# mainboard.net
KiCad netlist of a schematic drawn in EAGLE
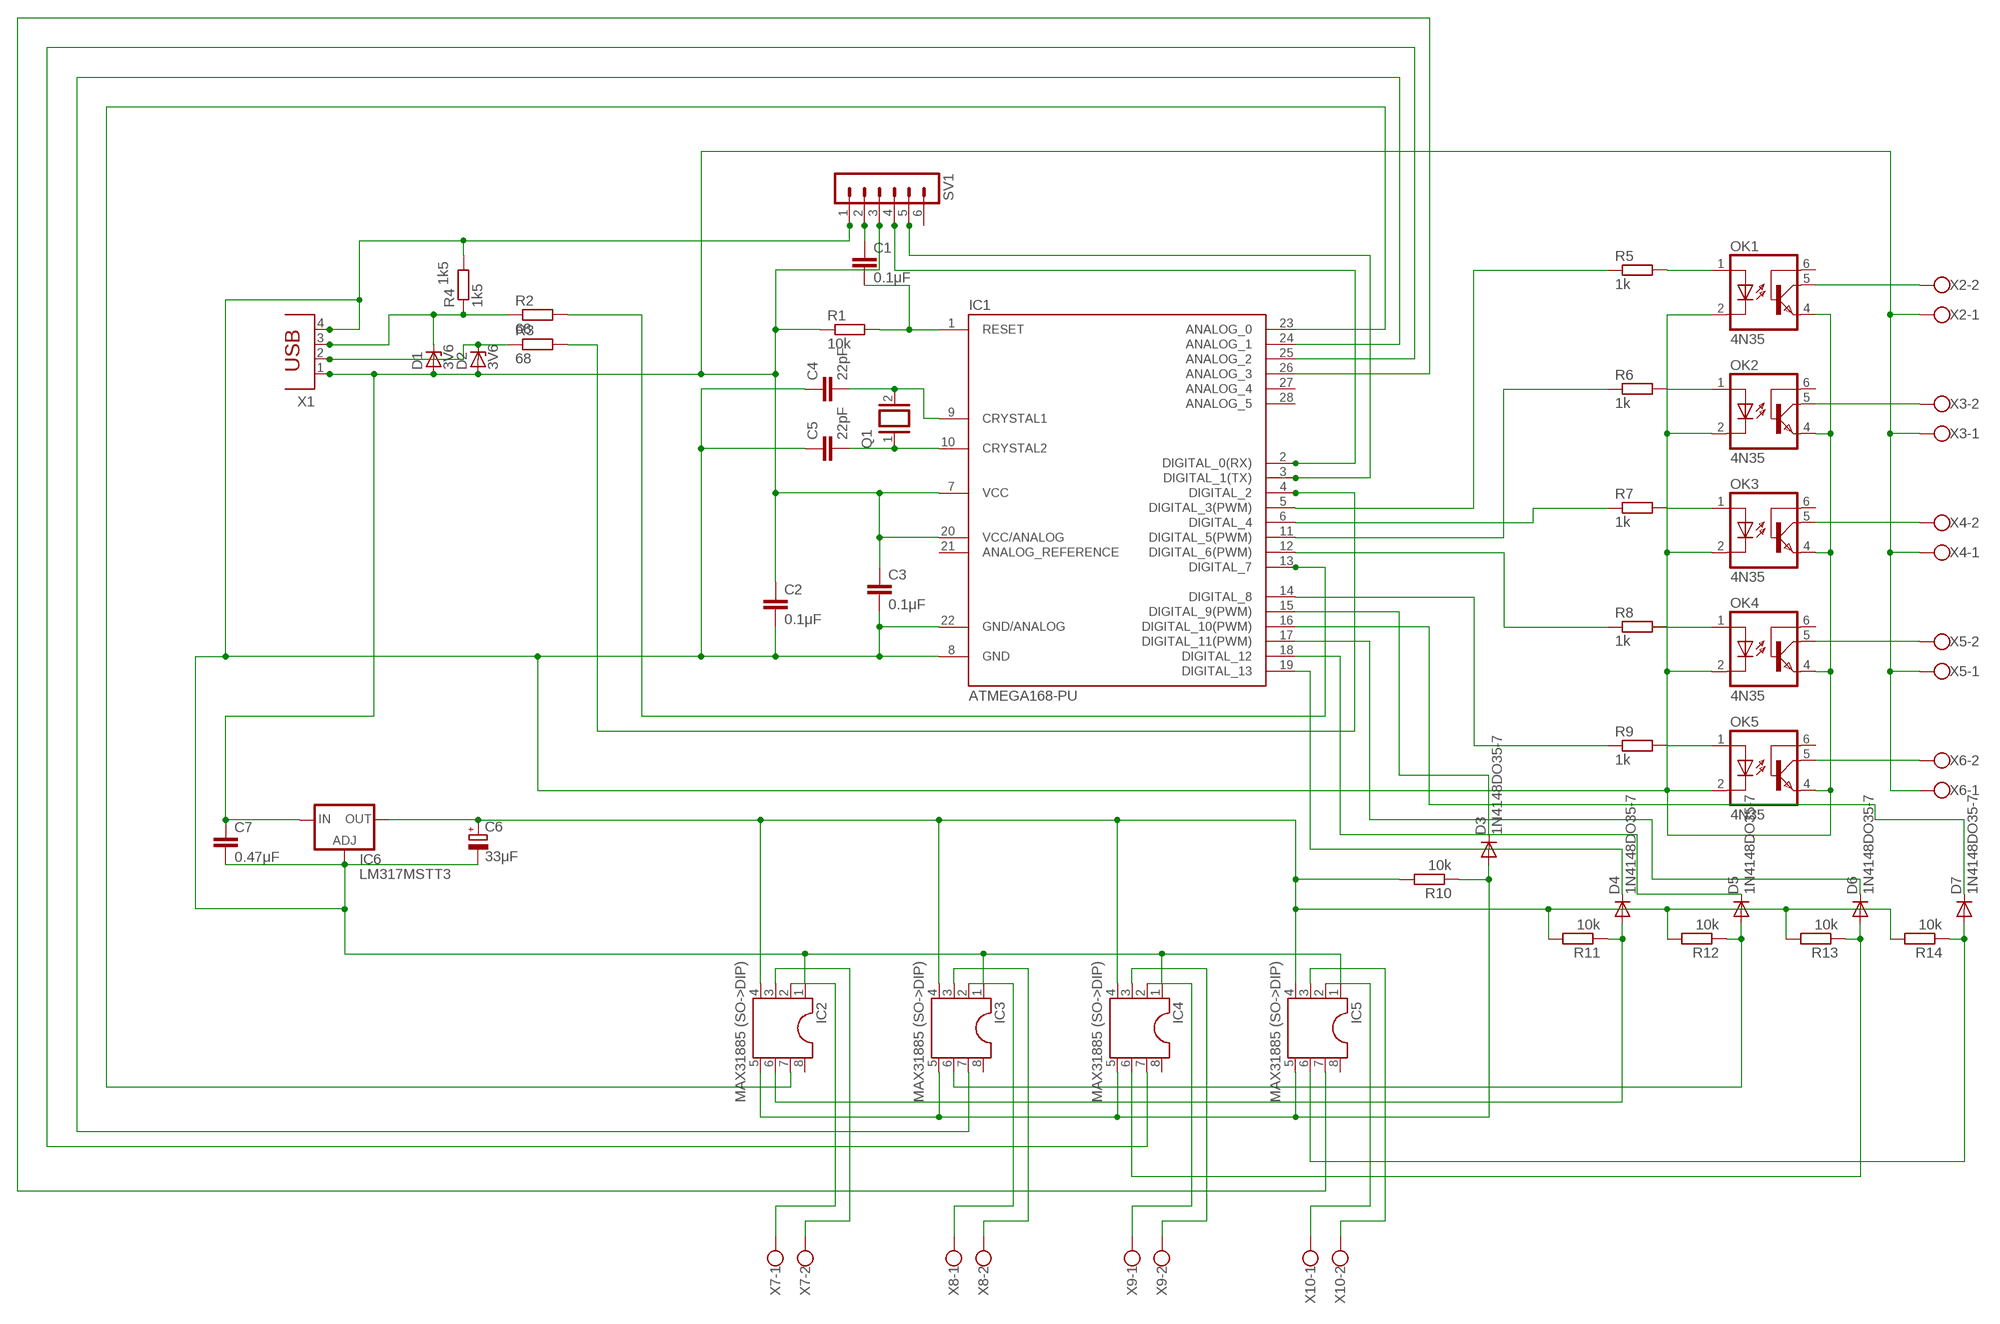
[diagram p0: schematic, sheet 1]

(export (version "E")
  (design (tool "Eeschema 10.0.6"))
  (components
    (comp (ref "C1")
      (value "0.1μF")
      (footprint "eagle-import:C2.5-3")
      (libsource (lib "eagle-import") (part "C2,5-3"))
    )
    (comp (ref "C2")
      (value "0.1μF")
      (footprint "eagle-import:C2.5-3")
      (libsource (lib "eagle-import") (part "C2,5-3"))
    )
    (comp (ref "C3")
      (value "0.1μF")
      (footprint "eagle-import:C2.5-3")
      (libsource (lib "eagle-import") (part "C2,5-3"))
    )
    (comp (ref "C4")
      (value "22pF")
      (footprint "eagle-import:C2.5-3")
      (libsource (lib "eagle-import") (part "C2,5-3"))
    )
    (comp (ref "C5")
      (value "22pF")
      (footprint "eagle-import:C2.5-3")
      (libsource (lib "eagle-import") (part "C2,5-3"))
    )
    (comp (ref "C6")
      (value "33μF")
      (footprint "eagle-import:153CLV-0605")
      (libsource (lib "eagle-import") (part "CPOL-EU153CLV-0605"))
    )
    (comp (ref "C7")
      (value "0.47μF")
      (footprint "eagle-import:C2.5-3")
      (libsource (lib "eagle-import") (part "C2,5-3"))
    )
    (comp (ref "D1")
      (value "3V6")
      (footprint "eagle-import:ZDIO-5")
      (libsource (lib "eagle-import") (part "ZENER-DIODEZD-5"))
    )
    (comp (ref "D2")
      (value "3V6")
      (footprint "eagle-import:ZDIO-5")
      (libsource (lib "eagle-import") (part "ZENER-DIODEZD-5"))
    )
    (comp (ref "D3")
      (value "1N4148DO35-7")
      (footprint "eagle-import:DO35-7")
      (libsource (lib "eagle-import") (part "1N4148DO35-7"))
    )
    (comp (ref "D4")
      (value "1N4148DO35-7")
      (footprint "eagle-import:DO35-7")
      (libsource (lib "eagle-import") (part "1N4148DO35-7"))
    )
    (comp (ref "D5")
      (value "1N4148DO35-7")
      (footprint "eagle-import:DO35-7")
      (libsource (lib "eagle-import") (part "1N4148DO35-7"))
    )
    (comp (ref "D6")
      (value "1N4148DO35-7")
      (footprint "eagle-import:DO35-7")
      (libsource (lib "eagle-import") (part "1N4148DO35-7"))
    )
    (comp (ref "D7")
      (value "1N4148DO35-7")
      (footprint "eagle-import:DO35-7")
      (libsource (lib "eagle-import") (part "1N4148DO35-7"))
    )
    (comp (ref "IC1")
      (value "ATMEGA168-PU")
      (footprint "eagle-import:DIL28-3")
      (libsource (lib "eagle-import") (part "ATMEGA168-PU"))
    )
    (comp (ref "IC2")
      (value "DIL8S")
      (footprint "eagle-import:SOCKET-08")
      (libsource (lib "eagle-import") (part "DIL8S"))
    )
    (comp (ref "IC3")
      (value "DIL8S")
      (footprint "eagle-import:SOCKET-08")
      (libsource (lib "eagle-import") (part "DIL8S"))
    )
    (comp (ref "IC4")
      (value "DIL8S")
      (footprint "eagle-import:SOCKET-08")
      (libsource (lib "eagle-import") (part "DIL8S"))
    )
    (comp (ref "IC5")
      (value "DIL8S")
      (footprint "eagle-import:SOCKET-08")
      (libsource (lib "eagle-import") (part "DIL8S"))
    )
    (comp (ref "IC6")
      (value "LM317MSTT3")
      (footprint "eagle-import:SOT223")
      (libsource (lib "eagle-import") (part "LM317?MSTT3"))
    )
    (comp (ref "OK1")
      (value "4N35")
      (footprint "eagle-import:DIL06")
      (fields (field (name "MF") "FAIRCHILD SEMICONDUCTOR"))
      (libsource (lib "eagle-import") (part "4N35"))
    )
    (comp (ref "OK2")
      (value "4N35")
      (footprint "eagle-import:DIL06")
      (fields (field (name "MF") "FAIRCHILD SEMICONDUCTOR"))
      (libsource (lib "eagle-import") (part "4N35"))
    )
    (comp (ref "OK3")
      (value "4N35")
      (footprint "eagle-import:DIL06")
      (fields (field (name "MF") "FAIRCHILD SEMICONDUCTOR"))
      (libsource (lib "eagle-import") (part "4N35"))
    )
    (comp (ref "OK4")
      (value "4N35")
      (footprint "eagle-import:DIL06")
      (fields (field (name "MF") "FAIRCHILD SEMICONDUCTOR"))
      (libsource (lib "eagle-import") (part "4N35"))
    )
    (comp (ref "OK5")
      (value "4N35")
      (footprint "eagle-import:DIL06")
      (fields (field (name "MF") "FAIRCHILD SEMICONDUCTOR"))
      (libsource (lib "eagle-import") (part "4N35"))
    )
    (comp (ref "Q1")
      (value "XTAL/S")
      (footprint "eagle-import:QS")
      (libsource (lib "eagle-import") (part "XTAL/S"))
    )
    (comp (ref "R1")
      (value "10k")
      (footprint "eagle-import:0204_7")
      (libsource (lib "eagle-import") (part "R-EU_0204/7"))
    )
    (comp (ref "R2")
      (value "68")
      (footprint "eagle-import:0204_7")
      (libsource (lib "eagle-import") (part "R-EU_0204/7"))
    )
    (comp (ref "R3")
      (value "68")
      (footprint "eagle-import:0204_7")
      (libsource (lib "eagle-import") (part "R-EU_0204/7"))
    )
    (comp (ref "R4")
      (value "1k5")
      (footprint "eagle-import:0204_7")
      (libsource (lib "eagle-import") (part "R-EU_0204/7"))
    )
    (comp (ref "R5")
      (value "1k")
      (footprint "eagle-import:0204_7")
      (libsource (lib "eagle-import") (part "R-EU_0204/7"))
    )
    (comp (ref "R6")
      (value "1k")
      (footprint "eagle-import:0204_7")
      (libsource (lib "eagle-import") (part "R-EU_0204/7"))
    )
    (comp (ref "R7")
      (value "1k")
      (footprint "eagle-import:0204_7")
      (libsource (lib "eagle-import") (part "R-EU_0204/7"))
    )
    (comp (ref "R8")
      (value "1k")
      (footprint "eagle-import:0204_7")
      (libsource (lib "eagle-import") (part "R-EU_0204/7"))
    )
    (comp (ref "R9")
      (value "1k")
      (footprint "eagle-import:0204_7")
      (libsource (lib "eagle-import") (part "R-EU_0204/7"))
    )
    (comp (ref "R10")
      (value "10k")
      (footprint "eagle-import:0204_7")
      (libsource (lib "eagle-import") (part "R-EU_0204/7"))
    )
    (comp (ref "R11")
      (value "10k")
      (footprint "eagle-import:0204_7")
      (libsource (lib "eagle-import") (part "R-EU_0204/7"))
    )
    (comp (ref "R12")
      (value "10k")
      (footprint "eagle-import:0204_7")
      (libsource (lib "eagle-import") (part "R-EU_0204/7"))
    )
    (comp (ref "R13")
      (value "10k")
      (footprint "eagle-import:0204_7")
      (libsource (lib "eagle-import") (part "R-EU_0204/7"))
    )
    (comp (ref "R14")
      (value "10k")
      (footprint "eagle-import:0204_7")
      (libsource (lib "eagle-import") (part "R-EU_0204/7"))
    )
    (comp (ref "SV1")
      (value "MA06-1")
      (footprint "eagle-import:MA06-1")
      (libsource (lib "eagle-import") (part "MA06-1"))
    )
    (comp (ref "X1")
      (value "PN61729")
      (footprint "eagle-import:PN61729")
      (libsource (lib "eagle-import") (part "PN61729"))
    )
    (comp (ref "X2")
      (value "W237-102")
      (footprint "eagle-import:W237-102")
      (fields (field (name "MPN") "237-102"))
      (libsource (lib "eagle-import") (part "W237-102"))
    )
    (comp (ref "X3")
      (value "W237-102")
      (footprint "eagle-import:W237-102")
      (fields (field (name "MPN") "237-102"))
      (libsource (lib "eagle-import") (part "W237-102"))
    )
    (comp (ref "X4")
      (value "W237-102")
      (footprint "eagle-import:W237-102")
      (fields (field (name "MPN") "237-102"))
      (libsource (lib "eagle-import") (part "W237-102"))
    )
    (comp (ref "X5")
      (value "W237-102")
      (footprint "eagle-import:W237-102")
      (fields (field (name "MPN") "237-102"))
      (libsource (lib "eagle-import") (part "W237-102"))
    )
    (comp (ref "X6")
      (value "W237-102")
      (footprint "eagle-import:W237-102")
      (fields (field (name "MPN") "237-102"))
      (libsource (lib "eagle-import") (part "W237-102"))
    )
    (comp (ref "X7")
      (value "W237-102")
      (footprint "eagle-import:W237-102")
      (fields (field (name "MPN") "237-102"))
      (libsource (lib "eagle-import") (part "W237-102"))
    )
    (comp (ref "X8")
      (value "W237-102")
      (footprint "eagle-import:W237-102")
      (fields (field (name "MPN") "237-102"))
      (libsource (lib "eagle-import") (part "W237-102"))
    )
    (comp (ref "X9")
      (value "W237-102")
      (footprint "eagle-import:W237-102")
      (fields (field (name "MPN") "237-102"))
      (libsource (lib "eagle-import") (part "W237-102"))
    )
    (comp (ref "X10")
      (value "W237-102")
      (footprint "eagle-import:W237-102")
      (fields (field (name "MPN") "237-102"))
      (libsource (lib "eagle-import") (part "W237-102"))
    )
  )
  (nets
    (net (code "1") (name "Net-(C1-Pad1)") (class "Default")
      (node (ref "C1") (pin "1") (pinfunction "1_1") (pintype "passive"))
      (node (ref "SV1") (pin "2") (pinfunction "2_2") (pintype "passive"))
    )
    (net (code "2") (name "Net-(D1-PadC)") (class "Default")
      (node (ref "D1") (pin "C") (pinfunction "C_C") (pintype "passive"))
      (node (ref "R2") (pin "1") (pinfunction "1_1") (pintype "passive"))
      (node (ref "R4") (pin "1") (pinfunction "1_1") (pintype "passive"))
      (node (ref "X1") (pin "3") (pinfunction "3_3") (pintype "passive"))
    )
    (net (code "3") (name "Net-(D2-PadC)") (class "Default")
      (node (ref "D2") (pin "C") (pinfunction "C_C") (pintype "passive"))
      (node (ref "R3") (pin "1") (pinfunction "1_1") (pintype "passive"))
      (node (ref "X1") (pin "2") (pinfunction "2_2") (pintype "passive"))
    )
    (net (code "4") (name "Net-(D3-PadA)") (class "Default")
      (node (ref "D3") (pin "A") (pinfunction "A_A") (pintype "passive"))
      (node (ref "IC2") (pin "5") (pinfunction "5_5") (pintype "passive"))
      (node (ref "IC3") (pin "5") (pinfunction "5_5") (pintype "passive"))
      (node (ref "IC4") (pin "5") (pinfunction "5_5") (pintype "passive"))
      (node (ref "IC5") (pin "5") (pinfunction "5_5") (pintype "passive"))
      (node (ref "R10") (pin "1") (pinfunction "1_1") (pintype "passive"))
    )
    (net (code "5") (name "Net-(D4-PadA)") (class "Default")
      (node (ref "D4") (pin "A") (pinfunction "A_A") (pintype "passive"))
      (node (ref "IC2") (pin "6") (pinfunction "6_6") (pintype "passive"))
      (node (ref "R11") (pin "1") (pinfunction "1_1") (pintype "passive"))
    )
    (net (code "6") (name "Net-(D5-PadA)") (class "Default")
      (node (ref "D5") (pin "A") (pinfunction "A_A") (pintype "passive"))
      (node (ref "IC3") (pin "6") (pinfunction "6_6") (pintype "passive"))
      (node (ref "R12") (pin "1") (pinfunction "1_1") (pintype "passive"))
    )
    (net (code "7") (name "Net-(D6-PadA)") (class "Default")
      (node (ref "D6") (pin "A") (pinfunction "A_A") (pintype "passive"))
      (node (ref "IC4") (pin "6") (pinfunction "6_6") (pintype "passive"))
      (node (ref "R13") (pin "1") (pinfunction "1_1") (pintype "passive"))
    )
    (net (code "8") (name "Net-(D7-PadA)") (class "Default")
      (node (ref "D7") (pin "A") (pinfunction "A_A") (pintype "passive"))
      (node (ref "IC5") (pin "6") (pinfunction "6_6") (pintype "passive"))
      (node (ref "R14") (pin "1") (pinfunction "1_1") (pintype "passive"))
    )
    (net (code "9") (name "Net-(IC1-ANALOG_0)") (class "Default")
      (node (ref "IC1") (pin "23") (pinfunction "ANALOG_0_23") (pintype "bidirectional"))
      (node (ref "IC2") (pin "7") (pinfunction "7_7") (pintype "passive"))
    )
    (net (code "10") (name "Net-(IC1-ANALOG_1)") (class "Default")
      (node (ref "IC1") (pin "24") (pinfunction "ANALOG_1_24") (pintype "bidirectional"))
      (node (ref "IC3") (pin "7") (pinfunction "7_7") (pintype "passive"))
    )
    (net (code "11") (name "Net-(IC1-ANALOG_2)") (class "Default")
      (node (ref "IC1") (pin "25") (pinfunction "ANALOG_2_25") (pintype "bidirectional"))
      (node (ref "IC4") (pin "7") (pinfunction "7_7") (pintype "passive"))
    )
    (net (code "12") (name "Net-(IC1-ANALOG_3)") (class "Default")
      (node (ref "IC1") (pin "26") (pinfunction "ANALOG_3_26") (pintype "bidirectional"))
      (node (ref "IC5") (pin "7") (pinfunction "7_7") (pintype "passive"))
    )
    (net (code "13") (name "Net-(IC1-CRYSTAL1)") (class "Default")
      (node (ref "C4") (pin "2") (pinfunction "2_2") (pintype "passive"))
      (node (ref "IC1") (pin "9") (pinfunction "CRYSTAL1_9") (pintype "bidirectional"))
      (node (ref "Q1") (pin "2") (pinfunction "2_2") (pintype "passive"))
    )
    (net (code "14") (name "Net-(IC1-CRYSTAL2)") (class "Default")
      (node (ref "C5") (pin "2") (pinfunction "2_2") (pintype "passive"))
      (node (ref "IC1") (pin "10") (pinfunction "CRYSTAL2_10") (pintype "bidirectional"))
      (node (ref "Q1") (pin "1") (pinfunction "1_1") (pintype "passive"))
    )
    (net (code "15") (name "Net-(IC1-DIGITAL_0(RX))") (class "Default")
      (node (ref "IC1") (pin "2") (pinfunction "DIGITAL_0(RX)_2") (pintype "bidirectional"))
      (node (ref "SV1") (pin "4") (pinfunction "4_4") (pintype "passive"))
    )
    (net (code "16") (name "Net-(IC1-DIGITAL_1(TX))") (class "Default")
      (node (ref "IC1") (pin "3") (pinfunction "DIGITAL_1(TX)_3") (pintype "bidirectional"))
      (node (ref "SV1") (pin "5") (pinfunction "5_5") (pintype "passive"))
    )
    (net (code "17") (name "Net-(IC1-DIGITAL_2)") (class "Default")
      (node (ref "IC1") (pin "4") (pinfunction "DIGITAL_2_4") (pintype "bidirectional"))
      (node (ref "R3") (pin "2") (pinfunction "2_2") (pintype "passive"))
    )
    (net (code "18") (name "Net-(IC1-DIGITAL_3(PWM))") (class "Default")
      (node (ref "IC1") (pin "5") (pinfunction "DIGITAL_3(PWM)_5") (pintype "bidirectional"))
      (node (ref "R5") (pin "1") (pinfunction "1_1") (pintype "passive"))
    )
    (net (code "19") (name "Net-(IC1-DIGITAL_4)") (class "Default")
      (node (ref "IC1") (pin "6") (pinfunction "DIGITAL_4_6") (pintype "bidirectional"))
      (node (ref "R7") (pin "1") (pinfunction "1_1") (pintype "passive"))
    )
    (net (code "20") (name "Net-(IC1-DIGITAL_5(PWM))") (class "Default")
      (node (ref "IC1") (pin "11") (pinfunction "DIGITAL_5(PWM)_11") (pintype "bidirectional"))
      (node (ref "R6") (pin "1") (pinfunction "1_1") (pintype "passive"))
    )
    (net (code "21") (name "Net-(IC1-DIGITAL_6(PWM))") (class "Default")
      (node (ref "IC1") (pin "12") (pinfunction "DIGITAL_6(PWM)_12") (pintype "bidirectional"))
      (node (ref "R8") (pin "1") (pinfunction "1_1") (pintype "passive"))
    )
    (net (code "22") (name "Net-(IC1-DIGITAL_7)") (class "Default")
      (node (ref "IC1") (pin "13") (pinfunction "DIGITAL_7_13") (pintype "bidirectional"))
      (node (ref "R2") (pin "2") (pinfunction "2_2") (pintype "passive"))
    )
    (net (code "23") (name "Net-(IC1-DIGITAL_8)") (class "Default")
      (node (ref "IC1") (pin "14") (pinfunction "DIGITAL_8_14") (pintype "bidirectional"))
      (node (ref "R9") (pin "1") (pinfunction "1_1") (pintype "passive"))
    )
    (net (code "24") (name "Net-(IC1-DIGITAL_9(PWM))") (class "Default")
      (node (ref "D3") (pin "C") (pinfunction "C_C") (pintype "passive"))
      (node (ref "IC1") (pin "15") (pinfunction "DIGITAL_9(PWM)_15") (pintype "bidirectional"))
    )
    (net (code "25") (name "Net-(IC1-DIGITAL_10(PWM))") (class "Default")
      (node (ref "D7") (pin "C") (pinfunction "C_C") (pintype "passive"))
      (node (ref "IC1") (pin "16") (pinfunction "DIGITAL_10(PWM)_16") (pintype "bidirectional"))
    )
    (net (code "26") (name "Net-(IC1-DIGITAL_11(PWM))") (class "Default")
      (node (ref "D6") (pin "C") (pinfunction "C_C") (pintype "passive"))
      (node (ref "IC1") (pin "17") (pinfunction "DIGITAL_11(PWM)_17") (pintype "bidirectional"))
    )
    (net (code "27") (name "Net-(IC1-DIGITAL_12)") (class "Default")
      (node (ref "D5") (pin "C") (pinfunction "C_C") (pintype "passive"))
      (node (ref "IC1") (pin "18") (pinfunction "DIGITAL_12_18") (pintype "bidirectional"))
    )
    (net (code "28") (name "Net-(IC1-DIGITAL_13)") (class "Default")
      (node (ref "D4") (pin "C") (pinfunction "C_C") (pintype "passive"))
      (node (ref "IC1") (pin "19") (pinfunction "DIGITAL_13_19") (pintype "bidirectional"))
    )
    (net (code "29") (name "Net-(IC1-GND)") (class "Default")
      (node (ref "C2") (pin "2") (pinfunction "2_2") (pintype "passive"))
      (node (ref "C3") (pin "2") (pinfunction "2_2") (pintype "passive"))
      (node (ref "C4") (pin "1") (pinfunction "1_1") (pintype "passive"))
      (node (ref "C5") (pin "1") (pinfunction "1_1") (pintype "passive"))
      (node (ref "C6") (pin "-") (pinfunction "-_-") (pintype "passive"))
      (node (ref "C7") (pin "2") (pinfunction "2_2") (pintype "passive"))
      (node (ref "IC1") (pin "22") (pinfunction "GND/ANALOG_22") (pintype "power_in"))
      (node (ref "IC1") (pin "8") (pinfunction "GND_8") (pintype "power_in"))
      (node (ref "IC2") (pin "1") (pinfunction "1_1") (pintype "passive"))
      (node (ref "IC3") (pin "1") (pinfunction "1_1") (pintype "passive"))
      (node (ref "IC4") (pin "1") (pinfunction "1_1") (pintype "passive"))
      (node (ref "IC5") (pin "1") (pinfunction "1_1") (pintype "passive"))
      (node (ref "IC6") (pin "1") (pinfunction "ADJ_1") (pintype "input"))
      (node (ref "OK1") (pin "2") (pinfunction "C_2") (pintype "passive"))
      (node (ref "OK1") (pin "4") (pinfunction "EMI_4") (pintype "passive"))
      (node (ref "OK2") (pin "2") (pinfunction "C_2") (pintype "passive"))
      (node (ref "OK2") (pin "4") (pinfunction "EMI_4") (pintype "passive"))
      (node (ref "OK3") (pin "2") (pinfunction "C_2") (pintype "passive"))
      (node (ref "OK3") (pin "4") (pinfunction "EMI_4") (pintype "passive"))
      (node (ref "OK4") (pin "2") (pinfunction "C_2") (pintype "passive"))
      (node (ref "OK4") (pin "4") (pinfunction "EMI_4") (pintype "passive"))
      (node (ref "OK5") (pin "2") (pinfunction "C_2") (pintype "passive"))
      (node (ref "OK5") (pin "4") (pinfunction "EMI_4") (pintype "passive"))
      (node (ref "R4") (pin "2") (pinfunction "2_2") (pintype "passive"))
      (node (ref "SV1") (pin "1") (pinfunction "1_1") (pintype "passive"))
      (node (ref "X1") (pin "4") (pinfunction "4_4") (pintype "passive"))
    )
    (net (code "30") (name "Net-(IC1-RESET)") (class "Default")
      (node (ref "C1") (pin "2") (pinfunction "2_2") (pintype "passive"))
      (node (ref "IC1") (pin "1") (pinfunction "RESET_1") (pintype "bidirectional"))
      (node (ref "R1") (pin "2") (pinfunction "2_2") (pintype "passive"))
    )
    (net (code "31") (name "Net-(IC1-VCC)") (class "Default")
      (node (ref "C2") (pin "1") (pinfunction "1_1") (pintype "passive"))
      (node (ref "C3") (pin "1") (pinfunction "1_1") (pintype "passive"))
      (node (ref "C7") (pin "1") (pinfunction "1_1") (pintype "passive"))
      (node (ref "D1") (pin "A") (pinfunction "A_A") (pintype "passive"))
      (node (ref "D2") (pin "A") (pinfunction "A_A") (pintype "passive"))
      (node (ref "IC1") (pin "20") (pinfunction "VCC/ANALOG_20") (pintype "passive"))
      (node (ref "IC1") (pin "7") (pinfunction "VCC_7") (pintype "power_in"))
      (node (ref "IC6") (pin "3") (pinfunction "IN_3") (pintype "input"))
      (node (ref "R1") (pin "1") (pinfunction "1_1") (pintype "passive"))
      (node (ref "SV1") (pin "3") (pinfunction "3_3") (pintype "passive"))
      (node (ref "X1") (pin "1") (pinfunction "1_1") (pintype "passive"))
      (node (ref "X2") (pin "1") (pinfunction "KL_1") (pintype "passive"))
      (node (ref "X3") (pin "1") (pinfunction "KL_1") (pintype "passive"))
      (node (ref "X4") (pin "1") (pinfunction "KL_1") (pintype "passive"))
      (node (ref "X5") (pin "1") (pinfunction "KL_1") (pintype "passive"))
      (node (ref "X6") (pin "1") (pinfunction "KL_1") (pintype "passive"))
    )
    (net (code "32") (name "Net-(IC6-OUT)") (class "Default")
      (node (ref "C6") (pin "+") (pinfunction "+_+") (pintype "passive"))
      (node (ref "IC2") (pin "4") (pinfunction "4_4") (pintype "passive"))
      (node (ref "IC3") (pin "4") (pinfunction "4_4") (pintype "passive"))
      (node (ref "IC4") (pin "4") (pinfunction "4_4") (pintype "passive"))
      (node (ref "IC5") (pin "4") (pinfunction "4_4") (pintype "passive"))
      (node (ref "IC6") (pin "4") (pinfunction "OUT_4") (pintype "passive"))
      (node (ref "R10") (pin "2") (pinfunction "2_2") (pintype "passive"))
      (node (ref "R11") (pin "2") (pinfunction "2_2") (pintype "passive"))
      (node (ref "R12") (pin "2") (pinfunction "2_2") (pintype "passive"))
      (node (ref "R13") (pin "2") (pinfunction "2_2") (pintype "passive"))
      (node (ref "R14") (pin "2") (pinfunction "2_2") (pintype "passive"))
    )
    (net (code "33") (name "Net-(OK1-A)") (class "Default")
      (node (ref "OK1") (pin "1") (pinfunction "A_1") (pintype "passive"))
      (node (ref "R5") (pin "2") (pinfunction "2_2") (pintype "passive"))
    )
    (net (code "34") (name "Net-(OK1-COL)") (class "Default")
      (node (ref "OK1") (pin "5") (pinfunction "COL_5") (pintype "passive"))
      (node (ref "X2") (pin "2") (pinfunction "KL_2") (pintype "passive"))
    )
    (net (code "35") (name "Net-(OK2-A)") (class "Default")
      (node (ref "OK2") (pin "1") (pinfunction "A_1") (pintype "passive"))
      (node (ref "R6") (pin "2") (pinfunction "2_2") (pintype "passive"))
    )
    (net (code "36") (name "Net-(OK2-COL)") (class "Default")
      (node (ref "OK2") (pin "5") (pinfunction "COL_5") (pintype "passive"))
      (node (ref "X3") (pin "2") (pinfunction "KL_2") (pintype "passive"))
    )
    (net (code "37") (name "Net-(OK3-A)") (class "Default")
      (node (ref "OK3") (pin "1") (pinfunction "A_1") (pintype "passive"))
      (node (ref "R7") (pin "2") (pinfunction "2_2") (pintype "passive"))
    )
    (net (code "38") (name "Net-(OK3-COL)") (class "Default")
      (node (ref "OK3") (pin "5") (pinfunction "COL_5") (pintype "passive"))
      (node (ref "X4") (pin "2") (pinfunction "KL_2") (pintype "passive"))
    )
    (net (code "39") (name "Net-(OK4-A)") (class "Default")
      (node (ref "OK4") (pin "1") (pinfunction "A_1") (pintype "passive"))
      (node (ref "R8") (pin "2") (pinfunction "2_2") (pintype "passive"))
    )
    (net (code "40") (name "Net-(OK4-COL)") (class "Default")
      (node (ref "OK4") (pin "5") (pinfunction "COL_5") (pintype "passive"))
      (node (ref "X5") (pin "2") (pinfunction "KL_2") (pintype "passive"))
    )
    (net (code "41") (name "Net-(OK5-A)") (class "Default")
      (node (ref "OK5") (pin "1") (pinfunction "A_1") (pintype "passive"))
      (node (ref "R9") (pin "2") (pinfunction "2_2") (pintype "passive"))
    )
    (net (code "42") (name "Net-(OK5-COL)") (class "Default")
      (node (ref "OK5") (pin "5") (pinfunction "COL_5") (pintype "passive"))
      (node (ref "X6") (pin "2") (pinfunction "KL_2") (pintype "passive"))
    )
    (net (code "43") (name "Net-(X7A-KL)") (class "Default")
      (node (ref "IC2") (pin "2") (pinfunction "2_2") (pintype "passive"))
      (node (ref "X7") (pin "1") (pinfunction "KL_1") (pintype "passive"))
    )
    (net (code "44") (name "Net-(X7B-KL)") (class "Default")
      (node (ref "IC2") (pin "3") (pinfunction "3_3") (pintype "passive"))
      (node (ref "X7") (pin "2") (pinfunction "KL_2") (pintype "passive"))
    )
    (net (code "45") (name "Net-(X8A-KL)") (class "Default")
      (node (ref "IC3") (pin "2") (pinfunction "2_2") (pintype "passive"))
      (node (ref "X8") (pin "1") (pinfunction "KL_1") (pintype "passive"))
    )
    (net (code "46") (name "Net-(X8B-KL)") (class "Default")
      (node (ref "IC3") (pin "3") (pinfunction "3_3") (pintype "passive"))
      (node (ref "X8") (pin "2") (pinfunction "KL_2") (pintype "passive"))
    )
    (net (code "47") (name "Net-(X9A-KL)") (class "Default")
      (node (ref "IC4") (pin "2") (pinfunction "2_2") (pintype "passive"))
      (node (ref "X9") (pin "1") (pinfunction "KL_1") (pintype "passive"))
    )
    (net (code "48") (name "Net-(X9B-KL)") (class "Default")
      (node (ref "IC4") (pin "3") (pinfunction "3_3") (pintype "passive"))
      (node (ref "X9") (pin "2") (pinfunction "KL_2") (pintype "passive"))
    )
    (net (code "49") (name "Net-(X10A-KL)") (class "Default")
      (node (ref "IC5") (pin "2") (pinfunction "2_2") (pintype "passive"))
      (node (ref "X10") (pin "1") (pinfunction "KL_1") (pintype "passive"))
    )
    (net (code "50") (name "Net-(X10B-KL)") (class "Default")
      (node (ref "IC5") (pin "3") (pinfunction "3_3") (pintype "passive"))
      (node (ref "X10") (pin "2") (pinfunction "KL_2") (pintype "passive"))
    )
    (net (code "51") (name "unconnected-(IC1-ANALOG_4-Pad27)") (class "Default")
      (node (ref "IC1") (pin "27") (pinfunction "ANALOG_4_27") (pintype "bidirectional"))
    )
    (net (code "52") (name "unconnected-(IC1-ANALOG_5-Pad28)") (class "Default")
      (node (ref "IC1") (pin "28") (pinfunction "ANALOG_5_28") (pintype "bidirectional"))
    )
    (net (code "53") (name "unconnected-(IC1-ANALOG_REFERENCE-Pad21)") (class "Default")
      (node (ref "IC1") (pin "21") (pinfunction "ANALOG_REFERENCE_21") (pintype "passive"))
    )
    (net (code "54") (name "unconnected-(IC2-Pad8)") (class "Default")
      (node (ref "IC2") (pin "8") (pinfunction "8_8") (pintype "passive"))
    )
    (net (code "55") (name "unconnected-(IC3-Pad8)") (class "Default")
      (node (ref "IC3") (pin "8") (pinfunction "8_8") (pintype "passive"))
    )
    (net (code "56") (name "unconnected-(IC4-Pad8)") (class "Default")
      (node (ref "IC4") (pin "8") (pinfunction "8_8") (pintype "passive"))
    )
    (net (code "57") (name "unconnected-(IC5-Pad8)") (class "Default")
      (node (ref "IC5") (pin "8") (pinfunction "8_8") (pintype "passive"))
    )
    (net (code "58") (name "unconnected-(OK1-BAS-Pad6)") (class "Default")
      (node (ref "OK1") (pin "6") (pinfunction "BAS_6") (pintype "passive"))
    )
    (net (code "59") (name "unconnected-(OK2-BAS-Pad6)") (class "Default")
      (node (ref "OK2") (pin "6") (pinfunction "BAS_6") (pintype "passive"))
    )
    (net (code "60") (name "unconnected-(OK3-BAS-Pad6)") (class "Default")
      (node (ref "OK3") (pin "6") (pinfunction "BAS_6") (pintype "passive"))
    )
    (net (code "61") (name "unconnected-(OK4-BAS-Pad6)") (class "Default")
      (node (ref "OK4") (pin "6") (pinfunction "BAS_6") (pintype "passive"))
    )
    (net (code "62") (name "unconnected-(OK5-BAS-Pad6)") (class "Default")
      (node (ref "OK5") (pin "6") (pinfunction "BAS_6") (pintype "passive"))
    )
    (net (code "63") (name "unconnected-(SV1-Pad6)") (class "Default")
      (node (ref "SV1") (pin "6") (pinfunction "6_6") (pintype "passive"))
    )
  )
)
